# P06_BCS1_HDMI_Framer.net
KiCad netlist of a schematic drawn in Altium Designer
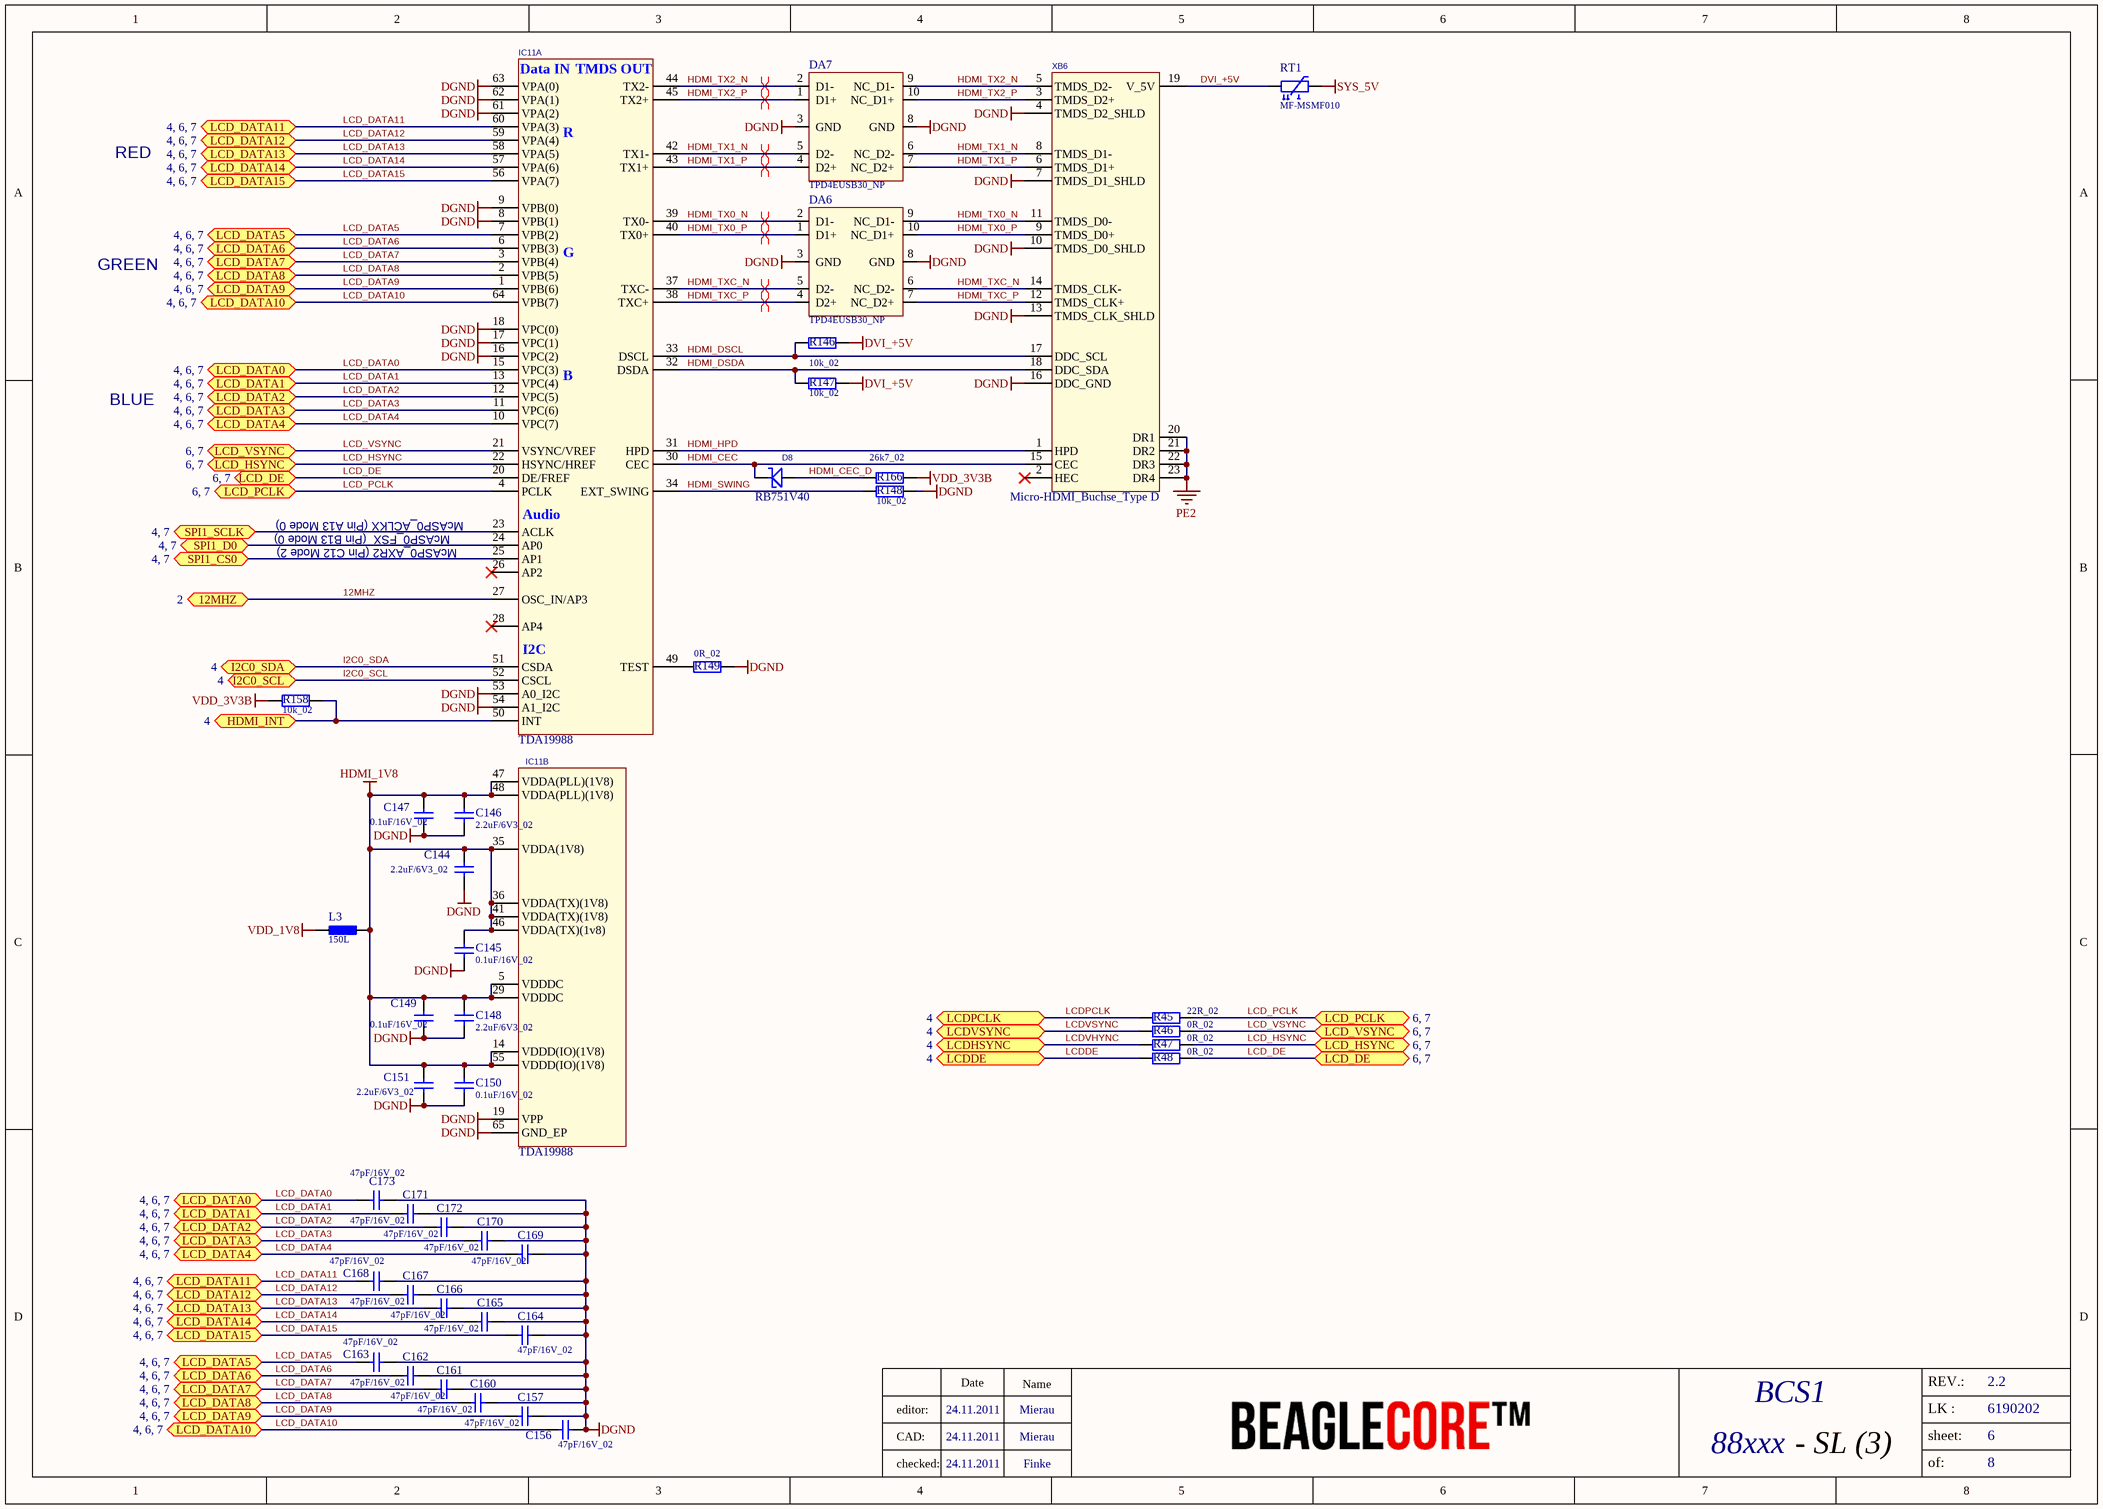
[diagram p0: P06_BCS1_HDMI Framer.SchDoc]

(export (version "E")
  (design (tool "Eeschema 10.0.6"))
  (components
    (comp (ref "C144")
      (value "2.2uF/6V3_02")
      (footprint "CC1005-0402")
      (description "Capacitor 0402;  6V3;  X5R")
      (libsource (lib "*") (part "C2.2uF/6V3_02"))
    )
    (comp (ref "C145")
      (value "0.1uF/16V_02")
      (footprint "CC1005-0402")
      (description "Capacitor 0402 16V Y5V")
      (libsource (lib "*") (part "C0.1uF/16V_02"))
    )
    (comp (ref "C146")
      (value "2.2uF/6V3_02")
      (footprint "CC1005-0402")
      (description "Capacitor 0402;  6V3;  X5R")
      (libsource (lib "*") (part "C2.2uF/6V3_02"))
    )
    (comp (ref "C147")
      (value "0.1uF/16V_02")
      (footprint "CC1005-0402")
      (description "Capacitor 0402 16V Y5V")
      (libsource (lib "*") (part "C0.1uF/16V_02"))
    )
    (comp (ref "C148")
      (value "2.2uF/6V3_02")
      (footprint "CC1005-0402")
      (description "Capacitor 0402;  6V3;  X5R")
      (libsource (lib "*") (part "C2.2uF/6V3_02"))
    )
    (comp (ref "C149")
      (value "0.1uF/16V_02")
      (footprint "CC1005-0402")
      (description "Capacitor 0402 16V Y5V")
      (libsource (lib "*") (part "C0.1uF/16V_02"))
    )
    (comp (ref "C150")
      (value "0.1uF/16V_02")
      (footprint "CC1005-0402")
      (description "Capacitor 0402 16V Y5V")
      (libsource (lib "*") (part "C0.1uF/16V_02"))
    )
    (comp (ref "C151")
      (value "2.2uF/6V3_02")
      (footprint "CC1005-0402")
      (description "Capacitor 0402;  6V3;  X5R")
      (libsource (lib "*") (part "C2.2uF/6V3_02"))
    )
    (comp (ref "C156")
      (value "47pF/16V_02")
      (footprint "CC1005-0402")
      (description "Capacitor 0402;  16V;  X7R")
      (libsource (lib "*") (part "C47pF/16V_02"))
    )
    (comp (ref "C157")
      (value "47pF/16V_02")
      (footprint "CC1005-0402")
      (description "Capacitor 0402;  16V;  X7R")
      (libsource (lib "*") (part "C47pF/16V_02"))
    )
    (comp (ref "C160")
      (value "47pF/16V_02")
      (footprint "CC1005-0402")
      (description "Capacitor 0402;  16V;  X7R")
      (libsource (lib "*") (part "C47pF/16V_02"))
    )
    (comp (ref "C161")
      (value "47pF/16V_02")
      (footprint "CC1005-0402")
      (description "Capacitor 0402;  16V;  X7R")
      (libsource (lib "*") (part "C47pF/16V_02"))
    )
    (comp (ref "C162")
      (value "47pF/16V_02")
      (footprint "CC1005-0402")
      (description "Capacitor 0402;  16V;  X7R")
      (libsource (lib "*") (part "C47pF/16V_02"))
    )
    (comp (ref "C163")
      (value "47pF/16V_02")
      (footprint "CC1005-0402")
      (description "Capacitor 0402;  16V;  X7R")
      (libsource (lib "*") (part "C47pF/16V_02"))
    )
    (comp (ref "C164")
      (value "47pF/16V_02")
      (footprint "CC1005-0402")
      (description "Capacitor 0402;  16V;  X7R")
      (libsource (lib "*") (part "C47pF/16V_02"))
    )
    (comp (ref "C165")
      (value "47pF/16V_02")
      (footprint "CC1005-0402")
      (description "Capacitor 0402;  16V;  X7R")
      (libsource (lib "*") (part "C47pF/16V_02"))
    )
    (comp (ref "C166")
      (value "47pF/16V_02")
      (footprint "CC1005-0402")
      (description "Capacitor 0402;  16V;  X7R")
      (libsource (lib "*") (part "C47pF/16V_02"))
    )
    (comp (ref "C167")
      (value "47pF/16V_02")
      (footprint "CC1005-0402")
      (description "Capacitor 0402;  16V;  X7R")
      (libsource (lib "*") (part "C47pF/16V_02"))
    )
    (comp (ref "C168")
      (value "47pF/16V_02")
      (footprint "CC1005-0402")
      (description "Capacitor 0402;  16V;  X7R")
      (libsource (lib "*") (part "C47pF/16V_02"))
    )
    (comp (ref "C169")
      (value "47pF/16V_02")
      (footprint "CC1005-0402")
      (description "Capacitor 0402;  16V;  X7R")
      (libsource (lib "*") (part "C47pF/16V_02"))
    )
    (comp (ref "C170")
      (value "47pF/16V_02")
      (footprint "CC1005-0402")
      (description "Capacitor 0402;  16V;  X7R")
      (libsource (lib "*") (part "C47pF/16V_02"))
    )
    (comp (ref "C171")
      (value "47pF/16V_02")
      (footprint "CC1005-0402")
      (description "Capacitor 0402;  16V;  X7R")
      (libsource (lib "*") (part "C47pF/16V_02"))
    )
    (comp (ref "C172")
      (value "47pF/16V_02")
      (footprint "CC1005-0402")
      (description "Capacitor 0402;  16V;  X7R")
      (libsource (lib "*") (part "C47pF/16V_02"))
    )
    (comp (ref "C173")
      (value "47pF/16V_02")
      (footprint "CC1005-0402")
      (description "Capacitor 0402;  16V;  X7R")
      (libsource (lib "*") (part "C47pF/16V_02"))
    )
    (comp (ref "D8")
      (value "RB751V40")
      (footprint "SOD323")
      (description "DIODE SCHOTTKY 40V 120MA SOD323")
      (libsource (lib "*") (part "DRB751V40"))
    )
    (comp (ref "DA6")
      (value "TPD4EUSB30_NP")
      (footprint "TPD4EUSB30")
      (description "Diode Array TVS,  for USB3.0; 4fach, N und P getauscht")
      (libsource (lib "*") (part "DATPD4EUSB30_NP"))
    )
    (comp (ref "DA7")
      (value "TPD4EUSB30_NP")
      (footprint "TPD4EUSB30")
      (description "Diode Array TVS,  for USB3.0; 4fach, N und P getauscht")
      (libsource (lib "*") (part "DATPD4EUSB30_NP"))
    )
    (comp (ref "IC11")
      (value "TDA19988")
      (footprint "HVQFN64+EP_N")
      (description "DP to HDMI ESD, Level Shifter")
      (libsource (lib "*") (part "ICTDA19988"))
    )
    (comp (ref "L3")
      (value "150L")
      (footprint "CR2012-0805")
      (description "Inductor 120 Ohm Ferrite 0805, 800mA")
      (libsource (lib "*") (part "L150 Ohm Ferrite"))
    )
    (comp (ref "R45")
      (value "22R_02")
      (footprint "CR1005-0402")
      (description "Resistor 0402")
      (libsource (lib "*") (part "R22R_02"))
    )
    (comp (ref "R46")
      (value "0R_02")
      (footprint "CR1005-0402")
      (description "Resistor 0402")
      (libsource (lib "*") (part "R0R_02"))
    )
    (comp (ref "R47")
      (value "0R_02")
      (footprint "CR1005-0402")
      (description "Resistor 0402")
      (libsource (lib "*") (part "R0R_02"))
    )
    (comp (ref "R48")
      (value "0R_02")
      (footprint "CR1005-0402")
      (description "Resistor 0402")
      (libsource (lib "*") (part "R0R_02"))
    )
    (comp (ref "R146")
      (value "10k_02")
      (footprint "CR1005-0402")
      (description "Resistor 0402")
      (libsource (lib "*") (part "R10k_02"))
    )
    (comp (ref "R147")
      (value "10k_02")
      (footprint "CR1005-0402")
      (description "Resistor 0402")
      (libsource (lib "") (part "R10k_02_1"))
    )
    (comp (ref "R148")
      (value "10k_02")
      (footprint "CR1005-0402")
      (description "Resistor 0402")
      (libsource (lib "*") (part "R10k_02"))
    )
    (comp (ref "R149")
      (value "0R_02")
      (footprint "CR1005-0402")
      (description "Resistor 0402")
      (libsource (lib "*") (part "R0R_02"))
    )
    (comp (ref "R158")
      (value "10k_02")
      (footprint "CR1005-0402")
      (description "Resistor 0402")
      (libsource (lib "*") (part "R10k_02"))
    )
    (comp (ref "R166")
      (value "26k7_02")
      (footprint "CR1005-0402")
      (description "Resistor 0402")
      (libsource (lib "*") (part "R26k7_02"))
    )
    (comp (ref "RT1")
      (value "MF-MSMF010")
      (footprint "FUSE-MF-MSMF")
      (description "resettable Fuse MF_MSMF 30V, 0,2A bei 23°C")
      (libsource (lib "*") (part "RTFUSE0.1A/30V"))
    )
    (comp (ref "XB6")
      (value "Micro-HDMI_Buchse_Type D")
      (description "micro HDMI Buchse SMT Type D")
      (libsource (lib "*") (part "XBU_Micro-HDMI_Buchse_Type D"))
    )
  )
  (nets
    (net (code "1") (name "/12MHZ") (class "Default")
      (node (ref "IC11") (pin "27") (pinfunction "OSC_IN/AP3_27") (pintype "passive"))
    )
    (net (code "2") (name "/HDMI_CEC") (class "Default")
      (node (ref "D8") (pin "1") (pinfunction "1_1") (pintype "passive"))
      (node (ref "IC11") (pin "30") (pinfunction "CEC_30") (pintype "passive"))
      (node (ref "XB6") (pin "15") (pinfunction "CEC_15") (pintype "passive"))
    )
    (net (code "3") (name "/HDMI_CEC_D") (class "Default")
      (node (ref "D8") (pin "2") (pinfunction "Anode_2") (pintype "passive"))
      (node (ref "R166") (pin "1") (pinfunction "1_1") (pintype "passive"))
    )
    (net (code "4") (name "/HDMI_DSCL") (class "Default")
      (node (ref "IC11") (pin "33") (pinfunction "DSCL_33") (pintype "passive"))
      (node (ref "R146") (pin "1") (pinfunction "1_1") (pintype "passive"))
      (node (ref "XB6") (pin "17") (pinfunction "DDC_SCL_17") (pintype "passive"))
    )
    (net (code "5") (name "/HDMI_DSDA") (class "Default")
      (node (ref "IC11") (pin "32") (pinfunction "DSDA_32") (pintype "passive"))
      (node (ref "R147") (pin "2") (pinfunction "2_2") (pintype "passive"))
      (node (ref "XB6") (pin "18") (pinfunction "DDC_SDA_18") (pintype "passive"))
    )
    (net (code "6") (name "/HDMI_HPD") (class "Default")
      (node (ref "IC11") (pin "31") (pinfunction "HPD_31") (pintype "passive"))
      (node (ref "XB6") (pin "1") (pinfunction "HPD_1") (pintype "passive"))
    )
    (net (code "7") (name "/HDMI_INT") (class "Default")
      (node (ref "IC11") (pin "50") (pinfunction "INT_50") (pintype "passive"))
      (node (ref "R158") (pin "2") (pinfunction "2_2") (pintype "passive"))
    )
    (net (code "8") (name "/HDMI_SWING") (class "Default")
      (node (ref "IC11") (pin "34") (pinfunction "EXT_SWING_34") (pintype "passive"))
      (node (ref "R148") (pin "1") (pinfunction "1_1") (pintype "passive"))
    )
    (net (code "9") (name "/HDMI_TX0_N") (class "Default")
      (node (ref "DA6") (pin "2") (pinfunction "D1-_2") (pintype "passive"))
      (node (ref "DA6") (pin "9") (pinfunction "NC_D1-_9") (pintype "passive"))
      (node (ref "IC11") (pin "39") (pinfunction "TX0-_39") (pintype "passive"))
      (node (ref "XB6") (pin "11") (pinfunction "TMDS_D0-_11") (pintype "passive"))
    )
    (net (code "10") (name "/HDMI_TX0_P") (class "Default")
      (node (ref "DA6") (pin "1") (pinfunction "D1+_1") (pintype "passive"))
      (node (ref "DA6") (pin "10") (pinfunction "NC_D1+_10") (pintype "passive"))
      (node (ref "IC11") (pin "40") (pinfunction "TX0+_40") (pintype "passive"))
      (node (ref "XB6") (pin "9") (pinfunction "TMDS_D0+_9") (pintype "passive"))
    )
    (net (code "11") (name "/HDMI_TX1_N") (class "Default")
      (node (ref "DA7") (pin "5") (pinfunction "D2-_5") (pintype "passive"))
      (node (ref "DA7") (pin "6") (pinfunction "NC_D2-_6") (pintype "passive"))
      (node (ref "IC11") (pin "42") (pinfunction "TX1-_42") (pintype "passive"))
      (node (ref "XB6") (pin "8") (pinfunction "TMDS_D1-_8") (pintype "passive"))
    )
    (net (code "12") (name "/HDMI_TX1_P") (class "Default")
      (node (ref "DA7") (pin "4") (pinfunction "D2+_4") (pintype "passive"))
      (node (ref "DA7") (pin "7") (pinfunction "NC_D2+_7") (pintype "passive"))
      (node (ref "IC11") (pin "43") (pinfunction "TX1+_43") (pintype "passive"))
      (node (ref "XB6") (pin "6") (pinfunction "TMDS_D1+_6") (pintype "passive"))
    )
    (net (code "13") (name "/HDMI_TX2_N") (class "Default")
      (node (ref "DA7") (pin "2") (pinfunction "D1-_2") (pintype "passive"))
      (node (ref "DA7") (pin "9") (pinfunction "NC_D1-_9") (pintype "passive"))
      (node (ref "IC11") (pin "44") (pinfunction "TX2-_44") (pintype "passive"))
      (node (ref "XB6") (pin "5") (pinfunction "TMDS_D2-_5") (pintype "passive"))
    )
    (net (code "14") (name "/HDMI_TX2_P") (class "Default")
      (node (ref "DA7") (pin "1") (pinfunction "D1+_1") (pintype "passive"))
      (node (ref "DA7") (pin "10") (pinfunction "NC_D1+_10") (pintype "passive"))
      (node (ref "IC11") (pin "45") (pinfunction "TX2+_45") (pintype "passive"))
      (node (ref "XB6") (pin "3") (pinfunction "TMDS_D2+_3") (pintype "passive"))
    )
    (net (code "15") (name "/HDMI_TXC_N") (class "Default")
      (node (ref "DA6") (pin "5") (pinfunction "D2-_5") (pintype "passive"))
      (node (ref "DA6") (pin "6") (pinfunction "NC_D2-_6") (pintype "passive"))
      (node (ref "IC11") (pin "37") (pinfunction "TXC-_37") (pintype "passive"))
      (node (ref "XB6") (pin "14") (pinfunction "TMDS_CLK-_14") (pintype "passive"))
    )
    (net (code "16") (name "/HDMI_TXC_P") (class "Default")
      (node (ref "DA6") (pin "4") (pinfunction "D2+_4") (pintype "passive"))
      (node (ref "DA6") (pin "7") (pinfunction "NC_D2+_7") (pintype "passive"))
      (node (ref "IC11") (pin "38") (pinfunction "TXC+_38") (pintype "passive"))
      (node (ref "XB6") (pin "12") (pinfunction "TMDS_CLK+_12") (pintype "passive"))
    )
    (net (code "17") (name "/I2C0_SCL") (class "Default")
      (node (ref "IC11") (pin "52") (pinfunction "CSCL_52") (pintype "passive"))
    )
    (net (code "18") (name "/I2C0_SDA") (class "Default")
      (node (ref "IC11") (pin "51") (pinfunction "CSDA_51") (pintype "passive"))
    )
    (net (code "19") (name "/LCDDE") (class "Default")
      (node (ref "R48") (pin "1") (pinfunction "1_1") (pintype "passive"))
    )
    (net (code "20") (name "/LCDPCLK") (class "Default")
      (node (ref "R45") (pin "1") (pinfunction "1_1") (pintype "passive"))
    )
    (net (code "21") (name "/LCDVHYNC") (class "Default")
      (node (ref "R47") (pin "1") (pinfunction "1_1") (pintype "passive"))
    )
    (net (code "22") (name "/LCDVSYNC") (class "Default")
      (node (ref "R46") (pin "1") (pinfunction "1_1") (pintype "passive"))
    )
    (net (code "23") (name "/LCD_DATA0") (class "Default")
      (node (ref "C173") (pin "1") (pinfunction "1_1") (pintype "passive"))
      (node (ref "IC11") (pin "15") (pinfunction "VPC(3)_15") (pintype "passive"))
    )
    (net (code "24") (name "/LCD_DATA1") (class "Default")
      (node (ref "C171") (pin "1") (pinfunction "1_1") (pintype "passive"))
      (node (ref "IC11") (pin "13") (pinfunction "VPC(4)_13") (pintype "passive"))
    )
    (net (code "25") (name "/LCD_DATA2") (class "Default")
      (node (ref "C172") (pin "1") (pinfunction "1_1") (pintype "passive"))
      (node (ref "IC11") (pin "12") (pinfunction "VPC(5)_12") (pintype "passive"))
    )
    (net (code "26") (name "/LCD_DATA3") (class "Default")
      (node (ref "C170") (pin "1") (pinfunction "1_1") (pintype "passive"))
      (node (ref "IC11") (pin "11") (pinfunction "VPC(6)_11") (pintype "passive"))
    )
    (net (code "27") (name "/LCD_DATA4") (class "Default")
      (node (ref "C169") (pin "1") (pinfunction "1_1") (pintype "passive"))
      (node (ref "IC11") (pin "10") (pinfunction "VPC(7)_10") (pintype "passive"))
    )
    (net (code "28") (name "/LCD_DATA5") (class "Default")
      (node (ref "C163") (pin "1") (pinfunction "1_1") (pintype "passive"))
      (node (ref "IC11") (pin "7") (pinfunction "VPB(2)_7") (pintype "passive"))
    )
    (net (code "29") (name "/LCD_DATA6") (class "Default")
      (node (ref "C162") (pin "1") (pinfunction "1_1") (pintype "passive"))
      (node (ref "IC11") (pin "6") (pinfunction "VPB(3)_6") (pintype "passive"))
    )
    (net (code "30") (name "/LCD_DATA7") (class "Default")
      (node (ref "C161") (pin "1") (pinfunction "1_1") (pintype "passive"))
      (node (ref "IC11") (pin "3") (pinfunction "VPB(4)_3") (pintype "passive"))
    )
    (net (code "31") (name "/LCD_DATA8") (class "Default")
      (node (ref "C160") (pin "1") (pinfunction "1_1") (pintype "passive"))
      (node (ref "IC11") (pin "2") (pinfunction "VPB(5)_2") (pintype "passive"))
    )
    (net (code "32") (name "/LCD_DATA9") (class "Default")
      (node (ref "C157") (pin "1") (pinfunction "1_1") (pintype "passive"))
      (node (ref "IC11") (pin "1") (pinfunction "VPB(6)_1") (pintype "passive"))
    )
    (net (code "33") (name "/LCD_DATA10") (class "Default")
      (node (ref "C156") (pin "1") (pinfunction "1_1") (pintype "passive"))
      (node (ref "IC11") (pin "64") (pinfunction "VPB(7)_64") (pintype "passive"))
    )
    (net (code "34") (name "/LCD_DATA11") (class "Default")
      (node (ref "C168") (pin "1") (pinfunction "1_1") (pintype "passive"))
      (node (ref "IC11") (pin "60") (pinfunction "VPA(3)_60") (pintype "passive"))
    )
    (net (code "35") (name "/LCD_DATA12") (class "Default")
      (node (ref "C167") (pin "1") (pinfunction "1_1") (pintype "passive"))
      (node (ref "IC11") (pin "59") (pinfunction "VPA(4)_59") (pintype "passive"))
    )
    (net (code "36") (name "/LCD_DATA13") (class "Default")
      (node (ref "C166") (pin "1") (pinfunction "1_1") (pintype "passive"))
      (node (ref "IC11") (pin "58") (pinfunction "VPA(5)_58") (pintype "passive"))
    )
    (net (code "37") (name "/LCD_DATA14") (class "Default")
      (node (ref "C165") (pin "1") (pinfunction "1_1") (pintype "passive"))
      (node (ref "IC11") (pin "57") (pinfunction "VPA(6)_57") (pintype "passive"))
    )
    (net (code "38") (name "/LCD_DATA15") (class "Default")
      (node (ref "C164") (pin "1") (pinfunction "1_1") (pintype "passive"))
      (node (ref "IC11") (pin "56") (pinfunction "VPA(7)_56") (pintype "passive"))
    )
    (net (code "39") (name "/LCD_DE") (class "Default")
      (node (ref "IC11") (pin "20") (pinfunction "DE/FREF_20") (pintype "passive"))
      (node (ref "R48") (pin "2") (pinfunction "2_2") (pintype "passive"))
    )
    (net (code "40") (name "/LCD_HSYNC") (class "Default")
      (node (ref "IC11") (pin "22") (pinfunction "HSYNC/HREF_22") (pintype "passive"))
      (node (ref "R47") (pin "2") (pinfunction "2_2") (pintype "passive"))
    )
    (net (code "41") (name "/LCD_PCLK") (class "Default")
      (node (ref "IC11") (pin "4") (pinfunction "PCLK_4") (pintype "passive"))
      (node (ref "R45") (pin "2") (pinfunction "2_2") (pintype "passive"))
    )
    (net (code "42") (name "/LCD_VSYNC") (class "Default")
      (node (ref "IC11") (pin "21") (pinfunction "VSYNC/VREF_21") (pintype "passive"))
      (node (ref "R46") (pin "2") (pinfunction "2_2") (pintype "passive"))
    )
    (net (code "43") (name "/SPI1_CS0") (class "Default")
      (node (ref "IC11") (pin "25") (pinfunction "AP1_25") (pintype "passive"))
    )
    (net (code "44") (name "/SPI1_D0") (class "Default")
      (node (ref "IC11") (pin "24") (pinfunction "AP0_24") (pintype "passive"))
    )
    (net (code "45") (name "/SPI1_SCLK") (class "Default")
      (node (ref "IC11") (pin "23") (pinfunction "ACLK_23") (pintype "passive"))
    )
    (net (code "46") (name "DGND") (class "Default")
      (node (ref "C144") (pin "1") (pinfunction "1_1") (pintype "passive"))
      (node (ref "C145") (pin "2") (pinfunction "2_2") (pintype "passive"))
      (node (ref "C146") (pin "1") (pinfunction "1_1") (pintype "passive"))
      (node (ref "C147") (pin "2") (pinfunction "2_2") (pintype "passive"))
      (node (ref "C148") (pin "1") (pinfunction "1_1") (pintype "passive"))
      (node (ref "C149") (pin "2") (pinfunction "2_2") (pintype "passive"))
      (node (ref "C150") (pin "2") (pinfunction "2_2") (pintype "passive"))
      (node (ref "C151") (pin "2") (pinfunction "2_2") (pintype "passive"))
      (node (ref "C156") (pin "2") (pinfunction "2_2") (pintype "passive"))
      (node (ref "C157") (pin "2") (pinfunction "2_2") (pintype "passive"))
      (node (ref "C160") (pin "2") (pinfunction "2_2") (pintype "passive"))
      (node (ref "C161") (pin "2") (pinfunction "2_2") (pintype "passive"))
      (node (ref "C162") (pin "2") (pinfunction "2_2") (pintype "passive"))
      (node (ref "C163") (pin "2") (pinfunction "2_2") (pintype "passive"))
      (node (ref "C164") (pin "2") (pinfunction "2_2") (pintype "passive"))
      (node (ref "C165") (pin "2") (pinfunction "2_2") (pintype "passive"))
      (node (ref "C166") (pin "2") (pinfunction "2_2") (pintype "passive"))
      (node (ref "C167") (pin "2") (pinfunction "2_2") (pintype "passive"))
      (node (ref "C168") (pin "2") (pinfunction "2_2") (pintype "passive"))
      (node (ref "C169") (pin "2") (pinfunction "2_2") (pintype "passive"))
      (node (ref "C170") (pin "2") (pinfunction "2_2") (pintype "passive"))
      (node (ref "C171") (pin "2") (pinfunction "2_2") (pintype "passive"))
      (node (ref "C172") (pin "2") (pinfunction "2_2") (pintype "passive"))
      (node (ref "C173") (pin "2") (pinfunction "2_2") (pintype "passive"))
      (node (ref "DA6") (pin "3") (pinfunction "GND_3") (pintype "passive"))
      (node (ref "DA6") (pin "8") (pinfunction "GND_8") (pintype "passive"))
      (node (ref "DA7") (pin "3") (pinfunction "GND_3") (pintype "passive"))
      (node (ref "DA7") (pin "8") (pinfunction "GND_8") (pintype "passive"))
      (node (ref "IC11") (pin "16") (pinfunction "VPC(2)_16") (pintype "passive"))
      (node (ref "IC11") (pin "17") (pinfunction "VPC(1)_17") (pintype "passive"))
      (node (ref "IC11") (pin "18") (pinfunction "VPC(0)_18") (pintype "passive"))
      (node (ref "IC11") (pin "19") (pinfunction "VPP_19") (pintype "passive"))
      (node (ref "IC11") (pin "53") (pinfunction "A0_I2C_53") (pintype "passive"))
      (node (ref "IC11") (pin "54") (pinfunction "A1_I2C_54") (pintype "passive"))
      (node (ref "IC11") (pin "61") (pinfunction "VPA(2)_61") (pintype "passive"))
      (node (ref "IC11") (pin "62") (pinfunction "VPA(1)_62") (pintype "passive"))
      (node (ref "IC11") (pin "63") (pinfunction "VPA(0)_63") (pintype "passive"))
      (node (ref "IC11") (pin "65") (pinfunction "GND_EP_65") (pintype "passive"))
      (node (ref "IC11") (pin "8") (pinfunction "VPB(1)_8") (pintype "passive"))
      (node (ref "IC11") (pin "9") (pinfunction "VPB(0)_9") (pintype "passive"))
      (node (ref "R148") (pin "2") (pinfunction "2_2") (pintype "passive"))
      (node (ref "R149") (pin "2") (pinfunction "2_2") (pintype "passive"))
      (node (ref "XB6") (pin "10") (pinfunction "TMDS_D0_SHLD_10") (pintype "passive"))
      (node (ref "XB6") (pin "13") (pinfunction "TMDS_CLK_SHLD_13") (pintype "passive"))
      (node (ref "XB6") (pin "16") (pinfunction "DDC_GND_16") (pintype "passive"))
      (node (ref "XB6") (pin "4") (pinfunction "TMDS_D2_SHLD_4") (pintype "passive"))
      (node (ref "XB6") (pin "7") (pinfunction "TMDS_D1_SHLD_7") (pintype "passive"))
    )
    (net (code "47") (name "DVI_+5V") (class "Default")
      (node (ref "R146") (pin "2") (pinfunction "2_2") (pintype "passive"))
      (node (ref "R147") (pin "1") (pinfunction "1_1") (pintype "passive"))
      (node (ref "RT1") (pin "2") (pinfunction "2_2") (pintype "passive"))
      (node (ref "XB6") (pin "19") (pinfunction "V_5V_19") (pintype "passive"))
    )
    (net (code "48") (name "HDMI_1V8") (class "Default")
      (node (ref "C144") (pin "2") (pinfunction "2_2") (pintype "passive"))
      (node (ref "C145") (pin "1") (pinfunction "1_1") (pintype "passive"))
      (node (ref "C146") (pin "2") (pinfunction "2_2") (pintype "passive"))
      (node (ref "C147") (pin "1") (pinfunction "1_1") (pintype "passive"))
      (node (ref "C148") (pin "2") (pinfunction "2_2") (pintype "passive"))
      (node (ref "C149") (pin "1") (pinfunction "1_1") (pintype "passive"))
      (node (ref "C150") (pin "1") (pinfunction "1_1") (pintype "passive"))
      (node (ref "C151") (pin "1") (pinfunction "1_1") (pintype "passive"))
      (node (ref "IC11") (pin "14") (pinfunction "VDDD(IO)(1V8)_14") (pintype "passive"))
      (node (ref "IC11") (pin "29") (pinfunction "VDDDC_29") (pintype "passive"))
      (node (ref "IC11") (pin "35") (pinfunction "VDDA(1V8)_35") (pintype "passive"))
      (node (ref "IC11") (pin "36") (pinfunction "VDDA(TX)(1V8)_36") (pintype "passive"))
      (node (ref "IC11") (pin "41") (pinfunction "VDDA(TX)(1V8)_41") (pintype "passive"))
      (node (ref "IC11") (pin "46") (pinfunction "VDDA(TX)(1v8)_46") (pintype "passive"))
      (node (ref "IC11") (pin "47") (pinfunction "VDDA(PLL)(1V8)_47") (pintype "passive"))
      (node (ref "IC11") (pin "48") (pinfunction "VDDA(PLL)(1V8)_48") (pintype "passive"))
      (node (ref "IC11") (pin "5") (pinfunction "VDDDC_5") (pintype "passive"))
      (node (ref "IC11") (pin "55") (pinfunction "VDDD(IO)(1V8)_55") (pintype "passive"))
      (node (ref "L3") (pin "1") (pinfunction "1_1") (pintype "passive"))
    )
    (net (code "49") (name "Net-(IC11A-TEST)") (class "Default")
      (node (ref "IC11") (pin "49") (pinfunction "TEST_49") (pintype "passive"))
      (node (ref "R149") (pin "1") (pinfunction "1_1") (pintype "passive"))
    )
    (net (code "50") (name "PE2") (class "Default")
      (node (ref "XB6") (pin "20") (pinfunction "DR1_20") (pintype "passive"))
      (node (ref "XB6") (pin "21") (pinfunction "DR2_21") (pintype "passive"))
      (node (ref "XB6") (pin "22") (pinfunction "DR3_22") (pintype "passive"))
      (node (ref "XB6") (pin "23") (pinfunction "DR4_23") (pintype "passive"))
    )
    (net (code "51") (name "SYS_5V") (class "Default")
      (node (ref "RT1") (pin "1") (pinfunction "1_1") (pintype "passive"))
    )
    (net (code "52") (name "VDD_1V8") (class "Default")
      (node (ref "L3") (pin "2") (pinfunction "2_2") (pintype "passive"))
    )
    (net (code "53") (name "VDD_3V3B") (class "Default")
      (node (ref "R158") (pin "1") (pinfunction "1_1") (pintype "passive"))
      (node (ref "R166") (pin "2") (pinfunction "2_2") (pintype "passive"))
    )
    (net (code "54") (name "unconnected-(IC11A-AP2-Pad26)") (class "Default")
      (node (ref "IC11") (pin "26") (pinfunction "AP2_26") (pintype "passive+no_connect"))
    )
    (net (code "55") (name "unconnected-(IC11A-AP4-Pad28)") (class "Default")
      (node (ref "IC11") (pin "28") (pinfunction "AP4_28") (pintype "passive+no_connect"))
    )
    (net (code "56") (name "unconnected-(XB6-HEC-Pad2)") (class "Default")
      (node (ref "XB6") (pin "2") (pinfunction "HEC_2") (pintype "passive+no_connect"))
    )
  )
)
